# power_amp_module.net
KiCad netlist of a schematic drawn in Altium Designer
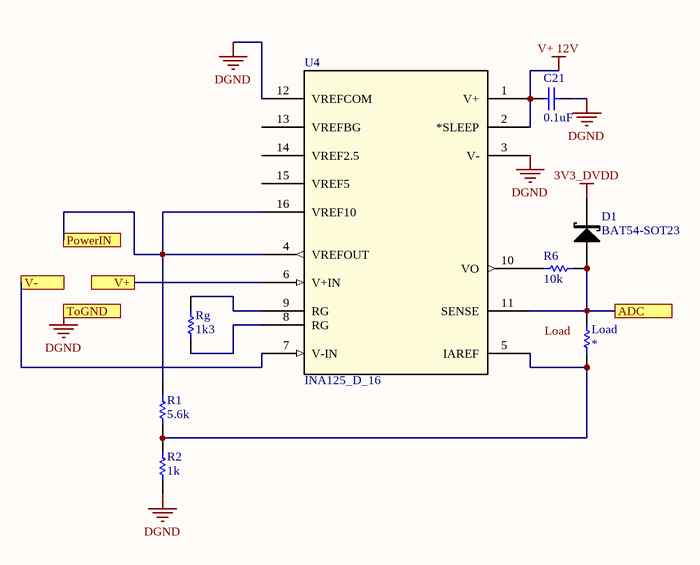
[diagram p0: power_amp_module.SchDoc]

(export (version "E")
  (design (tool "Eeschema 10.0.6"))
  (components
    (comp (ref "C21")
      (value "0.1uF")
      (footprint "C0805")
      (description "0805 Capacitor")
      (libsource (lib "PARSEC") (part "C0805"))
    )
    (comp (ref "D1")
      (value "BAT54-SOT23")
      (footprint "SOT23-DIODE")
      (description "SINGLE SHOTTKY DIODE")
      (fields
        (field (name "MANUFACTURER") "NXP Semiconductors")
        (field (name "MANUFACTURER PART NUMBER") "BAT54,215")
      )
      (libsource (lib "SMD Diodes") (part "BAT54-SOT23"))
    )
    (comp (ref "Load")
      (value "*")
      (footprint "R0603")
      (description "RESISTOR 0603")
      (fields (field (name "ALTIUM_VALUE") "*"))
      (libsource (lib "PARSEC") (part "R0603"))
    )
    (comp (ref "R1")
      (value "5.6k")
      (footprint "R0805")
      (description "RESISTOR 0805")
      (libsource (lib "PARSEC") (part "R0805"))
    )
    (comp (ref "R2")
      (value "1k")
      (footprint "R0805")
      (description "RESISTOR 0805")
      (libsource (lib "PARSEC") (part "R0805"))
    )
    (comp (ref "R6")
      (value "10k")
      (footprint "R0805")
      (description "RESISTOR 0805")
      (libsource (lib "PARSEC") (part "R0805"))
    )
    (comp (ref "Rg")
      (value "1k3")
      (footprint "R0603")
      (description "RESISTOR 0603")
      (libsource (lib "PARSEC") (part "R0603"))
    )
    (comp (ref "U4")
      (value "INA125_D_16")
      (footprint "D16")
      (description "Imported")
      (fields (field (name "MANUFACTURER") "Texas Instruments") (field (name "GENERIC_PART_NUMBER") "INA125"))
      (libsource (lib "PARSEC") (part "INA125_D_16"))
    )
  )
  (nets
    (net (code "1") (name "/ADC") (class "Default")
      (node (ref "D1") (pin "A") (pinfunction "1_A") (pintype "passive"))
      (node (ref "Load") (pin "2") (pinfunction "2_2") (pintype "passive"))
      (node (ref "R6") (pin "1") (pinfunction "1_1") (pintype "passive"))
      (node (ref "U4") (pin "11") (pinfunction "SENSE_11") (pintype "passive"))
    )
    (net (code "3") (name "/PowerIN") (class "Default")
      (node (ref "R1") (pin "2") (pinfunction "2_2") (pintype "passive"))
      (node (ref "U4") (pin "16") (pinfunction "VREF10_16") (pintype "power_in"))
      (node (ref "U4") (pin "4") (pinfunction "VREFOUT_4") (pintype "output"))
    )
    (net (code "4") (name "/V+") (class "Default")
      (node (ref "U4") (pin "6") (pinfunction "V+IN_6") (pintype "input"))
    )
    (net (code "5") (name "/V-") (class "Default")
      (node (ref "U4") (pin "7") (pinfunction "V-IN_7") (pintype "input"))
    )
    (net (code "6") (name "3V3_DVDD") (class "Default")
      (node (ref "D1") (pin "K") (pinfunction "3_K") (pintype "passive"))
    )
    (net (code "7") (name "DGND") (class "Default")
      (node (ref "C21") (pin "2") (pinfunction "2_2") (pintype "passive"))
      (node (ref "R2") (pin "1") (pinfunction "1_1") (pintype "passive"))
      (node (ref "U4") (pin "12") (pinfunction "VREFCOM_12") (pintype "power_in"))
      (node (ref "U4") (pin "3") (pinfunction "V-_3") (pintype "power_in"))
    )
    (net (code "8") (name "Net-(Rg-Pad1)") (class "Default")
      (node (ref "Rg") (pin "1") (pinfunction "1_1") (pintype "passive"))
      (node (ref "U4") (pin "8") (pinfunction "RG_8") (pintype "passive"))
    )
    (net (code "9") (name "Net-(Rg-Pad2)") (class "Default")
      (node (ref "Rg") (pin "2") (pinfunction "2_2") (pintype "passive"))
      (node (ref "U4") (pin "9") (pinfunction "RG_9") (pintype "passive"))
    )
    (net (code "10") (name "Net-(U4-IAREF)") (class "Default")
      (node (ref "Load") (pin "1") (pinfunction "1_1") (pintype "passive"))
      (node (ref "R1") (pin "1") (pinfunction "1_1") (pintype "passive"))
      (node (ref "R2") (pin "2") (pinfunction "2_2") (pintype "passive"))
      (node (ref "U4") (pin "5") (pinfunction "IAREF_5") (pintype "passive"))
    )
    (net (code "11") (name "Net-(U4-VO)") (class "Default")
      (node (ref "R6") (pin "2") (pinfunction "2_2") (pintype "passive"))
      (node (ref "U4") (pin "10") (pinfunction "VO_10") (pintype "output"))
    )
    (net (code "12") (name "V+ 12V") (class "Default")
      (node (ref "C21") (pin "1") (pinfunction "1_1") (pintype "passive"))
      (node (ref "U4") (pin "1") (pinfunction "V+_1") (pintype "power_in"))
      (node (ref "U4") (pin "2") (pinfunction "*SLEEP_2") (pintype "passive"))
    )
    (net (code "13") (name "unconnected-(U4-VREF2.5-Pad14)") (class "Default")
      (node (ref "U4") (pin "14") (pinfunction "VREF2.5_14") (pintype "power_in"))
    )
    (net (code "14") (name "unconnected-(U4-VREF5-Pad15)") (class "Default")
      (node (ref "U4") (pin "15") (pinfunction "VREF5_15") (pintype "power_in"))
    )
    (net (code "15") (name "unconnected-(U4-VREFBG-Pad13)") (class "Default")
      (node (ref "U4") (pin "13") (pinfunction "VREFBG_13") (pintype "power_in"))
    )
  )
)
